# fxloop.net
KiCad netlist of a schematic drawn in Altium Designer
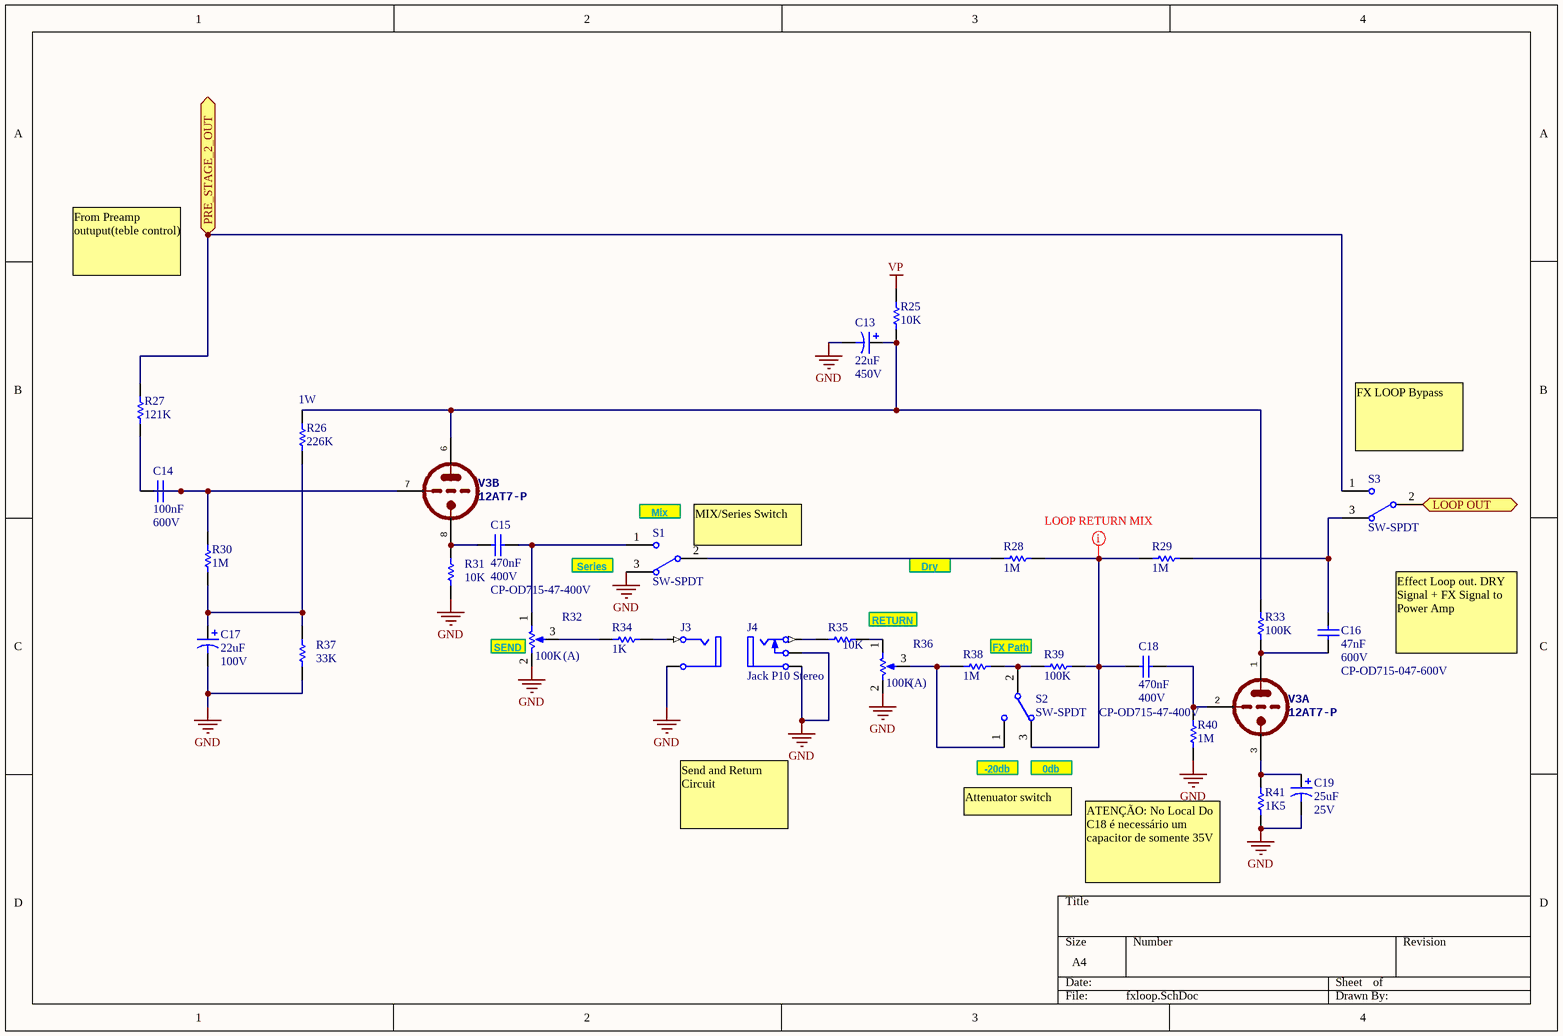
[diagram p0: fxloop.SchDoc]

(export (version "E")
  (design (tool "Eeschema 10.0.6"))
  (components
    (comp (ref "C13")
      (value "22uF")
      (footprint "RAD-POL-7.6-15")
      (description "Polarized Capacitor (Axial)")
      (fields
        (field (name "VOLTAGE") "450V")
        (field (name "Comment") "Cap Pol Rad")
        (field (name "PUBLISHER") "Altium Limited")
      )
      (libsource (lib "capacitors") (part "Cap Pol Rad"))
    )
    (comp (ref "C14")
      (value "100nF")
      (footprint "ORANGE-DROP-100nF")
      (description "Capacitor")
      (fields
        (field (name "VOLTAGE") "600V")
        (field (name "Comment") "Orange Drop Capacitor")
        (field (name "PUBLISHER") "Altium Limited")
      )
      (libsource (lib "capacitors") (part "Cap-Orange-DROP_600V"))
    )
    (comp (ref "C15")
      (value "470nF")
      (footprint "ORANGE-DROP-470-nF-400V")
      (description "Capacitor")
      (fields
        (field (name "MANUFACTURERPARTNUMBER") "715P47494M")
        (field (name "VOLTAGE") "400V")
        (field (name "TUBE_DEPOT_SN") "CP-OD715-47-400V")
        (field (name "Comment") "Orange Drop Capacitor")
        (field (name "PUBLISHER") "Linda HB Amplifiers")
      )
      (libsource (lib "capacitors") (part "Cap-Orange-DROP-470nF-400V"))
    )
    (comp (ref "C16")
      (value "47nF")
      (footprint "ORANGE-DROP-47nF-600V")
      (description "Capacitor")
      (fields
        (field (name "MANUFACTURERPARTNUMBER") "715P47396L")
        (field (name "VOLTAGE") "600V")
        (field (name "TUBEDEPOT_SN") "CP-OD715-047-600V")
        (field (name "Comment") "Orange Drop Capacitor")
        (field (name "PUBLISHER") "Linda HB Amps")
      )
      (libsource (lib "capacitors") (part "Cap-Orange-DROP-47nF-600V"))
    )
    (comp (ref "C17")
      (value "22uF")
      (footprint "RAD-POL-16x20x7.5")
      (description "Vishay 22uF 100V Polarized Capacitor (Radial); 2 Leads")
      (fields
        (field (name "PART NUMBER") "142 RHS")
        (field (name "VOLTAGE") "100V")
        (field (name "Comment") "Cap Pol Radial Vishay 22uF 100V")
        (field (name "PUBLISHER") "Altium Limited")
      )
      (libsource (lib "capacitors") (part "Cap Pol Radial Vishay 22uF 100V"))
    )
    (comp (ref "C18")
      (value "470nF")
      (footprint "ORANGE-DROP-470-nF-400V")
      (description "Capacitor")
      (fields
        (field (name "MANUFACTURERPARTNUMBER") "715P47494M")
        (field (name "VOLTAGE") "400V")
        (field (name "TUBE_DEPOT_SN") "CP-OD715-47-400V")
        (field (name "Comment") "Orange Drop Capacitor")
        (field (name "PUBLISHER") "Linda HB Amplifiers")
      )
      (libsource (lib "capacitors") (part "Cap-Orange-DROP-470nF-400V"))
    )
    (comp (ref "C19")
      (value "25uF")
      (footprint "AXIAL-POL-30mm")
      (description "Polarized Capacitor Axial")
      (fields
        (field (name "VOLTAGE") "25V")
        (field (name "Comment") "Cap Pol Axial")
        (field (name "PUBLISHER") "Whitesheep Amps")
      )
      (libsource (lib "capacitors") (part "Cap Pol Axial"))
    )
    (comp (ref "J3")
      (value "Jack Mono")
      (footprint "JACK-MONO-PCB-MINI")
      (description "Jack Socket, Thru-Hole, Vertical, 2-Conductor Open Circuit")
      (fields (field (name "PUBLISHER") "Altium Limited"))
      (libsource (lib "jacks") (part "Jack Moto P10"))
    )
    (comp (ref "J4")
      (value "Jack P10 Stereo")
      (footprint "JACK-STEREO-3PAD")
      (description "Jack Socket, 1/4\" [6.5mm], Thru-Hole, Vertical, 2-Conductor with Tip closed")
      (fields (field (name "PUBLISHER") "Altium Limited"))
      (libsource (lib "jacks") (part "Jack P10 Stereo"))
    )
    (comp (ref "R25")
      (value "10K")
      (footprint "AXIAL-0.6")
      (description "Semiconductor Resistor")
      (fields
        (field (name "POWER") "1/2W")
        (field (name "Comment") "Metal Film Resistor 1/2W")
        (field (name "PUBLISHER") "Whitesheep Amps")
      )
      (libsource (lib "resistors") (part "Res Metal Film 1/2W"))
    )
    (comp (ref "R26")
      (value "226K")
      (footprint "AXIAL-0.6")
      (description "Semiconductor Resistor")
      (fields
        (field (name "POWER") "1W")
        (field (name "Comment") "Metal Film Resistor 1/2W")
        (field (name "PUBLISHER") "Whitesheep Amps")
      )
      (libsource (lib "resistors") (part "Res Metal Film 1/2W"))
    )
    (comp (ref "R27")
      (value "121K")
      (footprint "AXIAL-0.6")
      (description "Semiconductor Resistor")
      (fields
        (field (name "POWER") "1/2W")
        (field (name "Comment") "Metal Film Resistor 1/2W")
        (field (name "PUBLISHER") "Whitesheep Amps")
      )
      (libsource (lib "resistors") (part "Res Metal Film 1/2W"))
    )
    (comp (ref "R28")
      (value "1M")
      (footprint "AXIAL-0.6")
      (description "Semiconductor Resistor")
      (fields
        (field (name "POWER") "1/2W")
        (field (name "Comment") "Metal Film Resistor 1/2W")
        (field (name "PUBLISHER") "Whitesheep Amps")
      )
      (libsource (lib "resistors") (part "Res Metal Film 1/2W"))
    )
    (comp (ref "R29")
      (value "1M")
      (footprint "AXIAL-0.6")
      (description "Semiconductor Resistor")
      (fields
        (field (name "POWER") "1/2W")
        (field (name "Comment") "Metal Film Resistor 1/2W")
        (field (name "PUBLISHER") "Whitesheep Amps")
      )
      (libsource (lib "resistors") (part "Res Metal Film 1/2W"))
    )
    (comp (ref "R30")
      (value "1M")
      (footprint "AXIAL-0.6")
      (description "Semiconductor Resistor")
      (fields
        (field (name "POWER") "1/2W")
        (field (name "Comment") "Metal Film Resistor 1/2W")
        (field (name "PUBLISHER") "Whitesheep Amps")
      )
      (libsource (lib "resistors") (part "Res Metal Film 1/2W"))
    )
    (comp (ref "R31")
      (value "10K")
      (footprint "AXIAL-0.6")
      (description "Semiconductor Resistor")
      (fields
        (field (name "POWER") "1/2W")
        (field (name "Comment") "Metal Film Resistor 1/2W")
        (field (name "PUBLISHER") "Whitesheep Amps")
      )
      (libsource (lib "resistors") (part "Res Metal Film 1/2W"))
    )
    (comp (ref "R32")
      (value "100K")
      (footprint "pot_alpha - 2.54mm")
      (description "Potentiometer")
      (fields
        (field (name "TYPE") "(A)")
        (field (name "Comment") "ALPHA Potentiometer")
        (field (name "PUBLISHER") "Altium Limited")
      )
      (libsource (lib "potentiometers") (part "alpha-pot"))
    )
    (comp (ref "R33")
      (value "100K")
      (footprint "AXIAL-0.6")
      (description "Semiconductor Resistor")
      (fields
        (field (name "POWER") "1/2W")
        (field (name "Comment") "Metal Film Resistor 1/2W")
        (field (name "PUBLISHER") "Whitesheep Amps")
      )
      (libsource (lib "resistors") (part "Res Metal Film 1/2W"))
    )
    (comp (ref "R34")
      (value "1K")
      (footprint "AXIAL-0.6")
      (description "Semiconductor Resistor")
      (fields
        (field (name "POWER") "1/2W")
        (field (name "Comment") "Metal Film Resistor 1/2W")
        (field (name "PUBLISHER") "Whitesheep Amps")
      )
      (libsource (lib "resistors") (part "Res Metal Film 1/2W"))
    )
    (comp (ref "R35")
      (value "10K")
      (footprint "AXIAL-0.6")
      (description "Semiconductor Resistor")
      (fields
        (field (name "POWER") "1/2W")
        (field (name "Comment") "Metal Film Resistor 1/2W")
        (field (name "PUBLISHER") "Whitesheep Amps")
      )
      (libsource (lib "resistors") (part "Res Metal Film 1/2W"))
    )
    (comp (ref "R36")
      (value "100K")
      (footprint "pot_alpha - 2.54mm")
      (description "Potentiometer")
      (fields
        (field (name "TYPE") "(A)")
        (field (name "Comment") "ALPHA Potentiometer")
        (field (name "PUBLISHER") "Altium Limited")
      )
      (libsource (lib "potentiometers") (part "alpha-pot"))
    )
    (comp (ref "R37")
      (value "33K")
      (footprint "AXIAL-0.6")
      (description "Semiconductor Resistor")
      (fields
        (field (name "POWER") "1/2W")
        (field (name "Comment") "Metal Film Resistor 1/2W")
        (field (name "PUBLISHER") "Whitesheep Amps")
      )
      (libsource (lib "resistors") (part "Res Metal Film 1/2W"))
    )
    (comp (ref "R38")
      (value "1M")
      (footprint "AXIAL-0.6")
      (description "Semiconductor Resistor")
      (fields
        (field (name "POWER") "1/2W")
        (field (name "Comment") "Metal Film Resistor 1/2W")
        (field (name "PUBLISHER") "Whitesheep Amps")
      )
      (libsource (lib "resistors") (part "Res Metal Film 1/2W"))
    )
    (comp (ref "R39")
      (value "100K")
      (footprint "AXIAL-0.6")
      (description "Semiconductor Resistor")
      (fields
        (field (name "POWER") "1/2W")
        (field (name "Comment") "Metal Film Resistor 1/2W")
        (field (name "PUBLISHER") "Whitesheep Amps")
      )
      (libsource (lib "resistors") (part "Res Metal Film 1/2W"))
    )
    (comp (ref "R40")
      (value "1M")
      (footprint "AXIAL-0.6")
      (description "Semiconductor Resistor")
      (fields
        (field (name "POWER") "1/2W")
        (field (name "Comment") "Metal Film Resistor 1/2W")
        (field (name "PUBLISHER") "Whitesheep Amps")
      )
      (libsource (lib "resistors") (part "Res Metal Film 1/2W"))
    )
    (comp (ref "R41")
      (value "1K5")
      (footprint "AXIAL-0.6")
      (description "Semiconductor Resistor")
      (fields
        (field (name "POWER") "1/2W")
        (field (name "Comment") "Metal Film Resistor 1/2W")
        (field (name "PUBLISHER") "Whitesheep Amps")
      )
      (libsource (lib "resistors") (part "Res Metal Film 1/2W"))
    )
    (comp (ref "S1")
      (value "SW-SPDT")
      (footprint "SPDT")
      (description "SPDT Subminiature Toggle Switch, Right Angle Mounting, Vertical Actuation")
      (fields (field (name "PUBLISHER") "Altium Limited"))
      (libsource (lib "switches") (part "SW-SPDT"))
    )
    (comp (ref "S2")
      (value "SW-SPDT")
      (footprint "SPDT")
      (description "SPDT Subminiature Toggle Switch, Right Angle Mounting, Vertical Actuation")
      (fields (field (name "PUBLISHER") "Altium Limited"))
      (libsource (lib "switches") (part "SW-SPDT"))
    )
    (comp (ref "S3")
      (value "SW-SPDT")
      (footprint "SPDT")
      (description "SPDT Subminiature Toggle Switch, Right Angle Mounting, Vertical Actuation")
      (fields (field (name "PUBLISHER") "Altium Limited"))
      (libsource (lib "switches") (part "SW-SPDT"))
    )
    (comp (ref "V3")
      (value "12AT7-P")
      (footprint "NOVAL")
      (libsource (lib "eagle_tubes_v6") (part "12AT7-P"))
    )
  )
  (nets
    (net (code "1") (name "/LOOP OUT") (class "Default")
      (node (ref "S3") (pin "2") (pinfunction "2_2") (pintype "passive"))
    )
    (net (code "2") (name "/PRE_STAGE_2_OUT") (class "Default")
      (node (ref "R27") (pin "2") (pinfunction "2_2") (pintype "passive"))
      (node (ref "S3") (pin "1") (pinfunction "1_1") (pintype "passive"))
    )
    (net (code "3") (name "GND") (class "Default")
      (node (ref "C13") (pin "2") (pinfunction "2_2") (pintype "passive"))
      (node (ref "C17") (pin "2") (pinfunction "2_2") (pintype "passive"))
      (node (ref "C19") (pin "2") (pinfunction "2_2") (pintype "passive"))
      (node (ref "J3") (pin "2") (pinfunction "S_2") (pintype "power_in"))
      (node (ref "J4") (pin "2") (pinfunction "TN_2") (pintype "passive"))
      (node (ref "J4") (pin "5") (pinfunction "S_5") (pintype "power_in"))
      (node (ref "R31") (pin "2") (pinfunction "2_2") (pintype "passive"))
      (node (ref "R32") (pin "2") (pinfunction "BOT_2") (pintype "passive"))
      (node (ref "R36") (pin "2") (pinfunction "BOT_2") (pintype "passive"))
      (node (ref "R37") (pin "2") (pinfunction "2_2") (pintype "passive"))
      (node (ref "R40") (pin "1") (pinfunction "1_1") (pintype "passive"))
      (node (ref "R41") (pin "1") (pinfunction "1_1") (pintype "passive"))
      (node (ref "S1") (pin "3") (pinfunction "3_3") (pintype "passive"))
    )
    (net (code "4") (name "Net-(C14-Pad1)") (class "Default")
      (node (ref "C14") (pin "1") (pinfunction "1_1") (pintype "passive"))
      (node (ref "R27") (pin "1") (pinfunction "1_1") (pintype "passive"))
    )
    (net (code "5") (name "Net-(C16-Pad2)") (class "Default")
      (node (ref "C16") (pin "2") (pinfunction "2_2") (pintype "passive"))
      (node (ref "R29") (pin "2") (pinfunction "2_2") (pintype "passive"))
      (node (ref "S3") (pin "3") (pinfunction "3_3") (pintype "passive"))
    )
    (net (code "6") (name "Net-(C17-Pad1)") (class "Default")
      (node (ref "C17") (pin "1") (pinfunction "1_1") (pintype "passive"))
      (node (ref "R26") (pin "2") (pinfunction "2_2") (pintype "passive"))
      (node (ref "R30") (pin "2") (pinfunction "2_2") (pintype "passive"))
      (node (ref "R37") (pin "1") (pinfunction "1_1") (pintype "passive"))
    )
    (net (code "7") (name "Net-(C18-Pad1)") (class "Default")
      (node (ref "C18") (pin "1") (pinfunction "1_1") (pintype "passive"))
      (node (ref "R28") (pin "2") (pinfunction "2_2") (pintype "passive"))
      (node (ref "R29") (pin "1") (pinfunction "1_1") (pintype "passive"))
      (node (ref "R39") (pin "2") (pinfunction "2_2") (pintype "passive"))
      (node (ref "S2") (pin "3") (pinfunction "3_3") (pintype "passive"))
    )
    (net (code "8") (name "Net-(J3-T)") (class "Default")
      (node (ref "J3") (pin "1") (pinfunction "T_1") (pintype "input"))
      (node (ref "R34") (pin "2") (pinfunction "2_2") (pintype "passive"))
    )
    (net (code "9") (name "Net-(J4-T)") (class "Default")
      (node (ref "J4") (pin "1") (pinfunction "T_1") (pintype "output"))
      (node (ref "R35") (pin "1") (pinfunction "1_1") (pintype "passive"))
    )
    (net (code "10") (name "Net-(R28-Pad1)") (class "Default")
      (node (ref "R28") (pin "1") (pinfunction "1_1") (pintype "passive"))
      (node (ref "S1") (pin "2") (pinfunction "2_2") (pintype "passive"))
    )
    (net (code "11") (name "Net-(R32-TAP)") (class "Default")
      (node (ref "R32") (pin "3") (pinfunction "TAP_3") (pintype "passive"))
      (node (ref "R34") (pin "1") (pinfunction "1_1") (pintype "passive"))
    )
    (net (code "12") (name "Net-(R32-TOP)") (class "Default")
      (node (ref "C15") (pin "2") (pinfunction "2_2") (pintype "passive"))
      (node (ref "R32") (pin "1") (pinfunction "TOP_1") (pintype "passive"))
      (node (ref "S1") (pin "1") (pinfunction "1_1") (pintype "passive"))
    )
    (net (code "13") (name "Net-(R36-TAP)") (class "Default")
      (node (ref "R36") (pin "3") (pinfunction "TAP_3") (pintype "passive"))
      (node (ref "R38") (pin "1") (pinfunction "1_1") (pintype "passive"))
      (node (ref "S2") (pin "1") (pinfunction "1_1") (pintype "passive"))
    )
    (net (code "14") (name "Net-(R36-TOP)") (class "Default")
      (node (ref "R35") (pin "2") (pinfunction "2_2") (pintype "passive"))
      (node (ref "R36") (pin "1") (pinfunction "TOP_1") (pintype "passive"))
    )
    (net (code "15") (name "Net-(R38-Pad2)") (class "Default")
      (node (ref "R38") (pin "2") (pinfunction "2_2") (pintype "passive"))
      (node (ref "R39") (pin "1") (pinfunction "1_1") (pintype "passive"))
      (node (ref "S2") (pin "2") (pinfunction "2_2") (pintype "passive"))
    )
    (net (code "16") (name "Net-(V3A-TA)") (class "Default")
      (node (ref "C16") (pin "1") (pinfunction "1_1") (pintype "passive"))
      (node (ref "R33") (pin "1") (pinfunction "1_1") (pintype "passive"))
      (node (ref "V3") (pin "1") (pinfunction "TA_1") (pintype "passive"))
    )
    (net (code "17") (name "Net-(V3A-TG)") (class "Default")
      (node (ref "C18") (pin "2") (pinfunction "2_2") (pintype "passive"))
      (node (ref "R40") (pin "2") (pinfunction "2_2") (pintype "passive"))
      (node (ref "V3") (pin "2") (pinfunction "TG_2") (pintype "passive"))
    )
    (net (code "18") (name "Net-(V3A-TK)") (class "Default")
      (node (ref "C19") (pin "1") (pinfunction "1_1") (pintype "passive"))
      (node (ref "R41") (pin "2") (pinfunction "2_2") (pintype "passive"))
      (node (ref "V3") (pin "3") (pinfunction "TK_3") (pintype "passive"))
    )
    (net (code "19") (name "Net-(V3B-TA)") (class "Default")
      (node (ref "C13") (pin "1") (pinfunction "1_1") (pintype "passive"))
      (node (ref "R25") (pin "1") (pinfunction "1_1") (pintype "passive"))
      (node (ref "R26") (pin "1") (pinfunction "1_1") (pintype "passive"))
      (node (ref "R33") (pin "2") (pinfunction "2_2") (pintype "passive"))
      (node (ref "V3") (pin "6") (pinfunction "TA_6") (pintype "passive"))
    )
    (net (code "20") (name "Net-(V3B-TG)") (class "Default")
      (node (ref "C14") (pin "2") (pinfunction "2_2") (pintype "passive"))
      (node (ref "R30") (pin "1") (pinfunction "1_1") (pintype "passive"))
      (node (ref "V3") (pin "7") (pinfunction "TG_7") (pintype "passive"))
    )
    (net (code "21") (name "Net-(V3B-TK)") (class "Default")
      (node (ref "C15") (pin "1") (pinfunction "1_1") (pintype "passive"))
      (node (ref "R31") (pin "1") (pinfunction "1_1") (pintype "passive"))
      (node (ref "V3") (pin "8") (pinfunction "TK_8") (pintype "passive"))
    )
    (net (code "22") (name "VP") (class "Default")
      (node (ref "R25") (pin "2") (pinfunction "2_2") (pintype "passive"))
    )
  )
)
